# Power_24V-3A.net
KiCad netlist of a schematic drawn in EAGLE
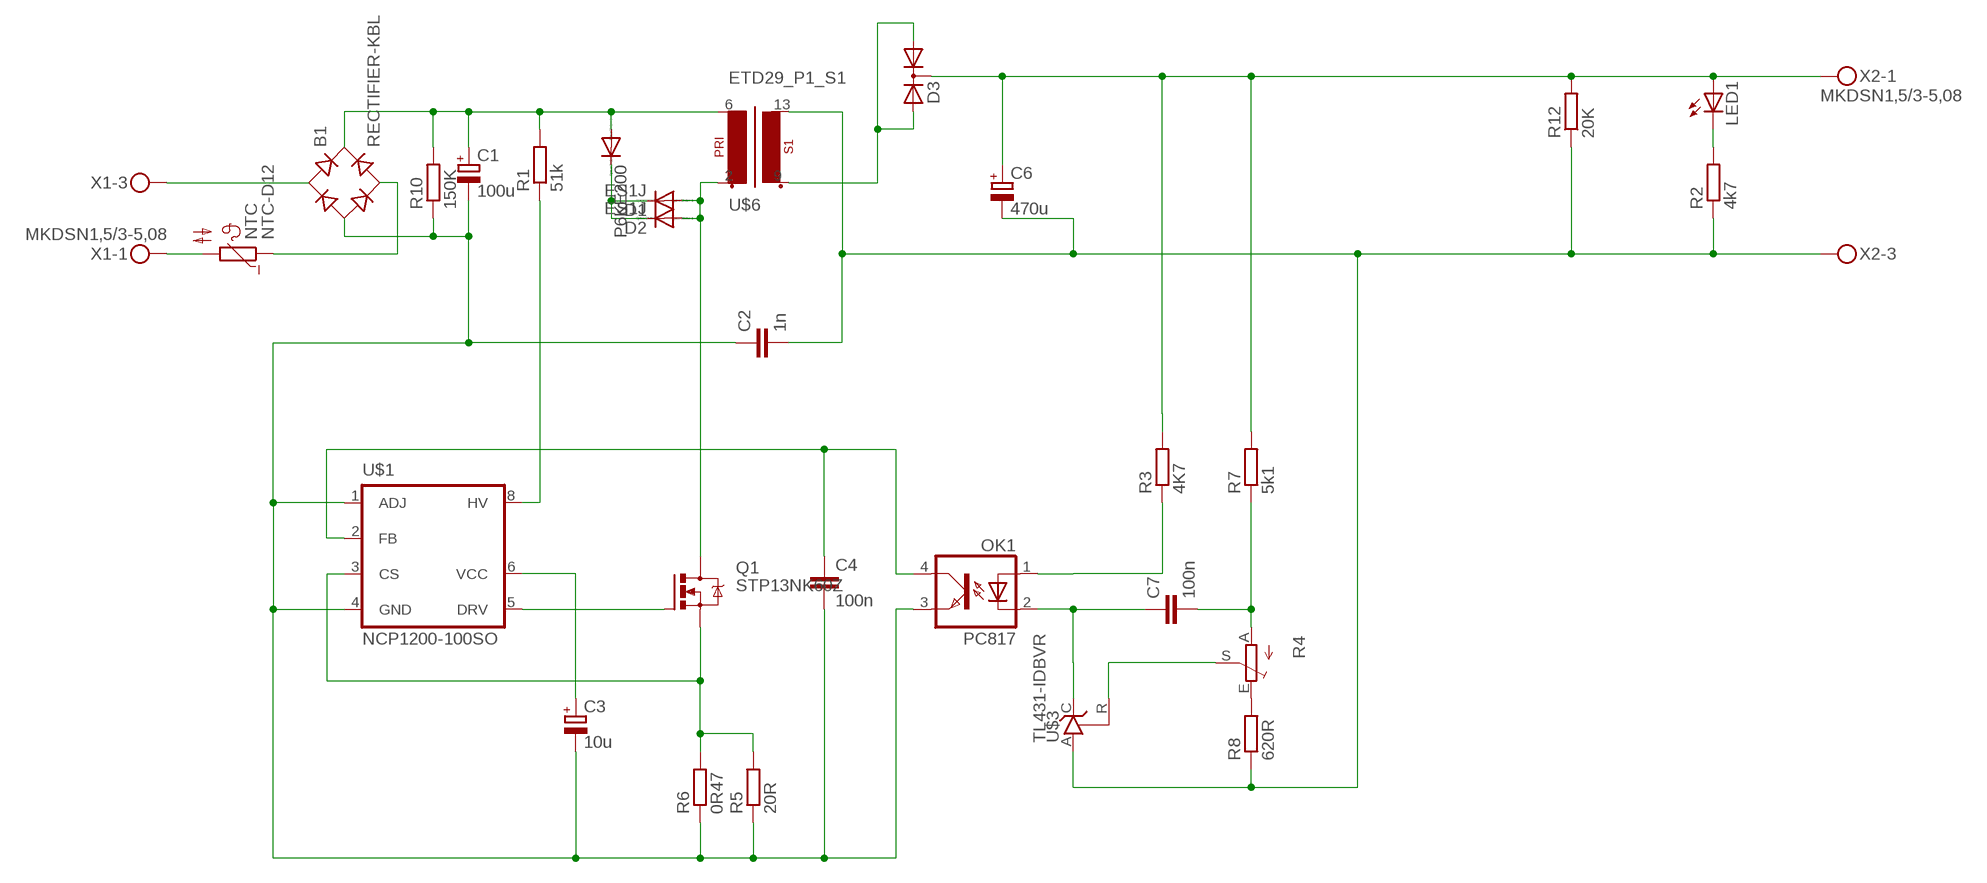
[diagram p0: schematic, sheet 1]

(export (version "E")
  (design (tool "Eeschema 10.0.6"))
  (components
    (comp (ref "B1")
      (value "RECTIFIER-KBL")
      (footprint "eagle-import:KBL")
      (libsource (lib "eagle-import") (part "RECTIFIER-KBL"))
    )
    (comp (ref "C1")
      (value "100u")
      (footprint "eagle-import:EB22,5D")
      (libsource (lib "eagle-import") (part "CPOL-EUE10-22.5"))
    )
    (comp (ref "C2")
      (value "1n")
      (footprint "eagle-import:C050-024X044")
      (libsource (lib "eagle-import") (part "C-EU050-024X044"))
    )
    (comp (ref "C3")
      (value "10u")
      (footprint "eagle-import:E5-5")
      (libsource (lib "eagle-import") (part "CPOL-EUE5-5"))
    )
    (comp (ref "C4")
      (value "100n")
      (footprint "eagle-import:C0805")
      (libsource (lib "eagle-import") (part "C-EUC0805"))
    )
    (comp (ref "C6")
      (value "470u")
      (footprint "eagle-import:E5-10,5")
      (libsource (lib "eagle-import") (part "CPOL-EUE5-10.5"))
    )
    (comp (ref "C7")
      (value "100n")
      (footprint "eagle-import:C0805")
      (libsource (lib "eagle-import") (part "C-EUC0805"))
    )
    (comp (ref "D1")
      (value "ES1J")
      (footprint "eagle-import:DO41-7.6")
      (libsource (lib "eagle-import") (part "DIODE-DO41-7.6"))
    )
    (comp (ref "D2")
      (value "ES1J")
      (footprint "eagle-import:DO41-7.6")
      (libsource (lib "eagle-import") (part "DIODE-DO41-7.6"))
    )
    (comp (ref "D3")
      (value "DIODE-2AC|CATO220V")
      (footprint "eagle-import:TO220ABS")
      (libsource (lib "eagle-import") (part "DIODE-2AC|CATO220V"))
    )
    (comp (ref "LED1")
      (value "LED5MM")
      (footprint "eagle-import:LED5MM")
      (libsource (lib "eagle-import") (part "LED5MM"))
    )
    (comp (ref "NTC")
      (value "NTC-D12")
      (footprint "eagle-import:NTC-D12")
      (libsource (lib "eagle-import") (part "NTC-D12"))
    )
    (comp (ref "OK1")
      (value "PC817")
      (footprint "eagle-import:DIL04")
      (fields (field (name "MPN") "PC817X4J000F"))
      (libsource (lib "eagle-import") (part "PC817"))
    )
    (comp (ref "P6KE200")
      (value "DIODE-DO15-12")
      (footprint "eagle-import:DO15-12")
      (libsource (lib "eagle-import") (part "DIODE-DO15-12"))
    )
    (comp (ref "Q1")
      (value "STP13NK60Z")
      (footprint "eagle-import:TO220BV")
      (libsource (lib "eagle-import") (part "IRF740"))
    )
    (comp (ref "R1")
      (value "51k")
      (footprint "eagle-import:SQP-5")
      (libsource (lib "eagle-import") (part "R_SQP-5"))
    )
    (comp (ref "R2")
      (value "4k7")
      (footprint "eagle-import:R1206")
      (libsource (lib "eagle-import") (part "R-EU_R1206"))
    )
    (comp (ref "R3")
      (value "4K7")
      (footprint "eagle-import:R1206")
      (libsource (lib "eagle-import") (part "R-EU_R1206"))
    )
    (comp (ref "R4")
      (value "TRIM_EU-S75H")
      (footprint "eagle-import:S75H")
      (libsource (lib "eagle-import") (part "TRIM_EU-S75H"))
    )
    (comp (ref "R5")
      (value "20R")
      (footprint "eagle-import:0411_12")
      (libsource (lib "eagle-import") (part "R-EU_0411/12"))
    )
    (comp (ref "R6")
      (value "0R47")
      (footprint "eagle-import:0411_12")
      (libsource (lib "eagle-import") (part "R-EU_0411/12"))
    )
    (comp (ref "R7")
      (value "5k1")
      (footprint "eagle-import:R1206")
      (libsource (lib "eagle-import") (part "R-EU_R1206"))
    )
    (comp (ref "R8")
      (value "620R")
      (footprint "eagle-import:R1206")
      (libsource (lib "eagle-import") (part "R-EU_R1206"))
    )
    (comp (ref "R10")
      (value "150K")
      (footprint "eagle-import:0207_10")
      (libsource (lib "eagle-import") (part "R-EU_0207/10"))
    )
    (comp (ref "R12")
      (value "20K")
      (footprint "eagle-import:R1206")
      (libsource (lib "eagle-import") (part "R-EU_R1206"))
    )
    (comp (ref "U$1")
      (value "NCP1200-100SO")
      (footprint "eagle-import:SOP8")
      (libsource (lib "eagle-import") (part "NCP1200-100SO"))
    )
    (comp (ref "U$3")
      (value "TL431-IDBVR")
      (footprint "eagle-import:SOT23-5")
      (libsource (lib "eagle-import") (part "TL431-IDBVR"))
    )
    (comp (ref "U$6")
      (value "ETD29_P1_S1")
      (footprint "eagle-import:ETD29")
      (libsource (lib "eagle-import") (part "ETD29_P1_S1"))
    )
    (comp (ref "X1")
      (value "MKDSN1,5/3-5,08")
      (footprint "eagle-import:MKDSN1,5_3-5,08")
      (libsource (lib "eagle-import") (part "MKDSN1,5/3-5,08"))
    )
    (comp (ref "X2")
      (value "MKDSN1,5/3-5,08")
      (footprint "eagle-import:MKDSN1,5_3-5,08")
      (libsource (lib "eagle-import") (part "MKDSN1,5/3-5,08"))
    )
  )
  (nets
    (net (code "1") (name "Net-(B1-PadAC2)") (class "Default")
      (node (ref "B1") (pin "AC2") (pinfunction "AC2_AC2") (pintype "passive"))
      (node (ref "NTC") (pin "1") (pinfunction "1_1") (pintype "passive"))
    )
    (net (code "2") (name "Net-(C7-Pad2)") (class "Default")
      (node (ref "C7") (pin "2") (pinfunction "2_2") (pintype "passive"))
      (node (ref "R4") (pin "A") (pinfunction "A_A") (pintype "passive"))
      (node (ref "R7") (pin "1") (pinfunction "1_1") (pintype "passive"))
    )
    (net (code "3") (name "Net-(D1-PadC)") (class "Default")
      (node (ref "D1") (pin "C") (pinfunction "C_C") (pintype "passive"))
      (node (ref "D2") (pin "C") (pinfunction "C_C") (pintype "passive"))
      (node (ref "P6KE200") (pin "C") (pinfunction "C_C") (pintype "passive"))
    )
    (net (code "4") (name "Net-(LED1-C)") (class "Default")
      (node (ref "LED1") (pin "K") (pinfunction "C_K") (pintype "passive"))
      (node (ref "R2") (pin "2") (pinfunction "2_2") (pintype "passive"))
    )
    (net (code "5") (name "Net-(OK1-A)") (class "Default")
      (node (ref "OK1") (pin "1") (pinfunction "A_1") (pintype "passive"))
      (node (ref "R3") (pin "1") (pinfunction "1_1") (pintype "passive"))
    )
    (net (code "6") (name "Net-(OK1-C)") (class "Default")
      (node (ref "C7") (pin "1") (pinfunction "1_1") (pintype "passive"))
      (node (ref "OK1") (pin "2") (pinfunction "C_2") (pintype "passive"))
      (node (ref "U$3") (pin "C") (pinfunction "C_C") (pintype "passive"))
    )
    (net (code "7") (name "Net-(OK1-COL)") (class "Default")
      (node (ref "C4") (pin "1") (pinfunction "1_1") (pintype "passive"))
      (node (ref "OK1") (pin "4") (pinfunction "COL_4") (pintype "passive"))
      (node (ref "U$1") (pin "2") (pinfunction "FB_2") (pintype "input"))
    )
    (net (code "8") (name "Net-(OK1-EMIT)") (class "Default")
      (node (ref "B1") (pin "-") (pinfunction "-_-") (pintype "passive"))
      (node (ref "C1") (pin "-") (pinfunction "-_-") (pintype "passive"))
      (node (ref "C2") (pin "1") (pinfunction "1_1") (pintype "passive"))
      (node (ref "C3") (pin "-") (pinfunction "-_-") (pintype "passive"))
      (node (ref "C4") (pin "2") (pinfunction "2_2") (pintype "passive"))
      (node (ref "OK1") (pin "3") (pinfunction "EMIT_3") (pintype "passive"))
      (node (ref "R10") (pin "1") (pinfunction "1_1") (pintype "passive"))
      (node (ref "R5") (pin "1") (pinfunction "1_1") (pintype "passive"))
      (node (ref "R6") (pin "1") (pinfunction "1_1") (pintype "passive"))
      (node (ref "U$1") (pin "1") (pinfunction "ADJ_1") (pintype "passive"))
      (node (ref "U$1") (pin "4") (pinfunction "GND_4") (pintype "passive"))
    )
    (net (code "9") (name "Net-(R4-PadE)") (class "Default")
      (node (ref "R4") (pin "E") (pinfunction "E_E") (pintype "passive"))
      (node (ref "R8") (pin "2") (pinfunction "2_2") (pintype "passive"))
    )
    (net (code "10") (name "Net-(R4-PadS)") (class "Default")
      (node (ref "R4") (pin "S") (pinfunction "S_S") (pintype "passive"))
      (node (ref "U$3") (pin "R") (pinfunction "R_R") (pintype "passive"))
    )
    (net (code "11") (name "Net-(U$1-CS)") (class "Default")
      (node (ref "Q1") (pin "S") (pinfunction "S_S") (pintype "passive"))
      (node (ref "R5") (pin "2") (pinfunction "2_2") (pintype "passive"))
      (node (ref "R6") (pin "2") (pinfunction "2_2") (pintype "passive"))
      (node (ref "U$1") (pin "3") (pinfunction "CS_3") (pintype "input"))
    )
    (net (code "12") (name "Net-(U$1-DRV)") (class "Default")
      (node (ref "Q1") (pin "G") (pinfunction "G_G") (pintype "passive"))
      (node (ref "U$1") (pin "5") (pinfunction "DRV_5") (pintype "power_in"))
    )
    (net (code "13") (name "Net-(U$1-HV)") (class "Default")
      (node (ref "R1") (pin "1") (pinfunction "1_1") (pintype "passive"))
      (node (ref "U$1") (pin "8") (pinfunction "HV_8") (pintype "passive"))
    )
    (net (code "14") (name "Net-(U$1-VCC)") (class "Default")
      (node (ref "C3") (pin "+") (pinfunction "+_+") (pintype "passive"))
      (node (ref "U$1") (pin "6") (pinfunction "VCC_6") (pintype "output"))
    )
    (net (code "15") (name "Net-(U$6-P1-1)") (class "Default")
      (node (ref "D1") (pin "A") (pinfunction "A_A") (pintype "passive"))
      (node (ref "D2") (pin "A") (pinfunction "A_A") (pintype "passive"))
      (node (ref "Q1") (pin "D") (pinfunction "D_D") (pintype "passive"))
      (node (ref "U$6") (pin "2") (pinfunction "P1-1_2") (pintype "passive"))
    )
    (net (code "16") (name "Net-(U$6-P1-2)") (class "Default")
      (node (ref "B1") (pin "+") (pinfunction "+_+") (pintype "passive"))
      (node (ref "C1") (pin "+") (pinfunction "+_+") (pintype "passive"))
      (node (ref "P6KE200") (pin "A") (pinfunction "A_A") (pintype "passive"))
      (node (ref "R1") (pin "2") (pinfunction "2_2") (pintype "passive"))
      (node (ref "R10") (pin "2") (pinfunction "2_2") (pintype "passive"))
      (node (ref "U$6") (pin "6") (pinfunction "P1-2_6") (pintype "passive"))
    )
    (net (code "17") (name "Net-(U$6-S1-1)") (class "Default")
      (node (ref "D3") (pin "A1") (pinfunction "A1_A1") (pintype "passive"))
      (node (ref "D3") (pin "A2") (pinfunction "A2_A2") (pintype "passive"))
      (node (ref "U$6") (pin "9") (pinfunction "S1-1_9") (pintype "passive"))
    )
    (net (code "18") (name "Net-(U$6-S1-2)") (class "Default")
      (node (ref "C2") (pin "2") (pinfunction "2_2") (pintype "passive"))
      (node (ref "C6") (pin "-") (pinfunction "-_-") (pintype "passive"))
      (node (ref "R12") (pin "1") (pinfunction "1_1") (pintype "passive"))
      (node (ref "R2") (pin "1") (pinfunction "1_1") (pintype "passive"))
      (node (ref "R8") (pin "1") (pinfunction "1_1") (pintype "passive"))
      (node (ref "U$3") (pin "A") (pinfunction "A_A") (pintype "passive"))
      (node (ref "U$6") (pin "13") (pinfunction "S1-2_13") (pintype "passive"))
      (node (ref "X2") (pin "3") (pinfunction "KL_3") (pintype "passive"))
    )
    (net (code "19") (name "Net-(X1A-KL)") (class "Default")
      (node (ref "NTC") (pin "2") (pinfunction "2_2") (pintype "passive"))
      (node (ref "X1") (pin "1") (pinfunction "KL_1") (pintype "passive"))
    )
    (net (code "20") (name "Net-(X1C-KL)") (class "Default")
      (node (ref "B1") (pin "AC1") (pinfunction "AC1_AC1") (pintype "passive"))
      (node (ref "X1") (pin "3") (pinfunction "KL_3") (pintype "passive"))
    )
    (net (code "21") (name "Net-(X2A-KL)") (class "Default")
      (node (ref "C6") (pin "+") (pinfunction "+_+") (pintype "passive"))
      (node (ref "D3") (pin "C") (pinfunction "C_C") (pintype "passive"))
      (node (ref "LED1") (pin "A") (pinfunction "A_A") (pintype "passive"))
      (node (ref "R12") (pin "2") (pinfunction "2_2") (pintype "passive"))
      (node (ref "R3") (pin "2") (pinfunction "2_2") (pintype "passive"))
      (node (ref "R7") (pin "2") (pinfunction "2_2") (pintype "passive"))
      (node (ref "X2") (pin "1") (pinfunction "KL_1") (pintype "passive"))
    )
  )
)
